# cblock.net
KiCad netlist of a schematic drawn in EAGLE
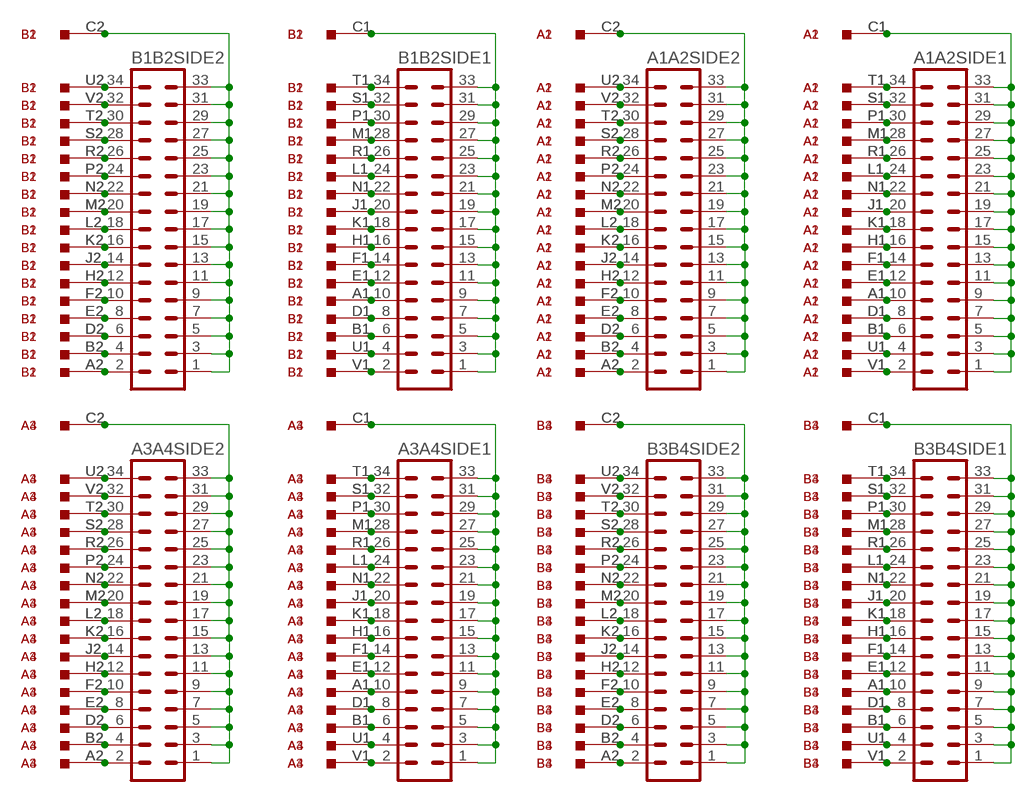
[diagram p0: schematic, sheet 1]

(export (version "E")
  (design (tool "Eeschema 10.0.6"))
  (components
    (comp (ref "A1")
      (value "M916")
      (footprint "eagle-import:H807")
      (libsource (lib "eagle-import") (part "M916"))
    )
    (comp (ref "A1A2SIDE1")
      (value "MA17-2")
      (footprint "eagle-import:MA17-2")
      (libsource (lib "eagle-import") (part "MA17-2"))
    )
    (comp (ref "A1A2SIDE2")
      (value "MA17-2")
      (footprint "eagle-import:MA17-2")
      (libsource (lib "eagle-import") (part "MA17-2"))
    )
    (comp (ref "A2")
      (value "M916")
      (footprint "eagle-import:H807")
      (libsource (lib "eagle-import") (part "M916"))
    )
    (comp (ref "A3")
      (value "M916")
      (footprint "eagle-import:H807")
      (libsource (lib "eagle-import") (part "M916"))
    )
    (comp (ref "A3A4SIDE1")
      (value "MA17-2")
      (footprint "eagle-import:MA17-2")
      (libsource (lib "eagle-import") (part "MA17-2"))
    )
    (comp (ref "A3A4SIDE2")
      (value "MA17-2")
      (footprint "eagle-import:MA17-2")
      (libsource (lib "eagle-import") (part "MA17-2"))
    )
    (comp (ref "A4")
      (value "M916")
      (footprint "eagle-import:H807")
      (libsource (lib "eagle-import") (part "M916"))
    )
    (comp (ref "B1")
      (value "M916")
      (footprint "eagle-import:H807")
      (libsource (lib "eagle-import") (part "M916"))
    )
    (comp (ref "B1B2SIDE1")
      (value "MA17-2")
      (footprint "eagle-import:MA17-2")
      (libsource (lib "eagle-import") (part "MA17-2"))
    )
    (comp (ref "B1B2SIDE2")
      (value "MA17-2")
      (footprint "eagle-import:MA17-2")
      (libsource (lib "eagle-import") (part "MA17-2"))
    )
    (comp (ref "B2")
      (value "M916")
      (footprint "eagle-import:H807")
      (libsource (lib "eagle-import") (part "M916"))
    )
    (comp (ref "B3")
      (value "M916")
      (footprint "eagle-import:H807")
      (libsource (lib "eagle-import") (part "M916"))
    )
    (comp (ref "B3B4SIDE1")
      (value "MA17-2")
      (footprint "eagle-import:MA17-2")
      (libsource (lib "eagle-import") (part "MA17-2"))
    )
    (comp (ref "B3B4SIDE2")
      (value "MA17-2")
      (footprint "eagle-import:MA17-2")
      (libsource (lib "eagle-import") (part "MA17-2"))
    )
    (comp (ref "B4")
      (value "M916")
      (footprint "eagle-import:H807")
      (libsource (lib "eagle-import") (part "M916"))
    )
  )
  (nets
    (net (code "1") (name "Net-(A1A-P$2)") (class "Default")
      (node (ref "A1") (pin "A1") (pinfunction "P$2_A1") (pintype "bidirectional"))
      (node (ref "A1A2SIDE1") (pin "10") (pinfunction "10_10") (pintype "passive"))
      (node (ref "A2") (pin "A1") (pinfunction "P$2_A1") (pintype "bidirectional"))
    )
    (net (code "2") (name "Net-(A1AA-P$2)") (class "Default")
      (node (ref "A1") (pin "R1") (pinfunction "P$2_R1") (pintype "bidirectional"))
      (node (ref "A1A2SIDE1") (pin "26") (pinfunction "26_26") (pintype "passive"))
      (node (ref "A2") (pin "R1") (pinfunction "P$2_R1") (pintype "bidirectional"))
    )
    (net (code "3") (name "Net-(A1AB-P$2)") (class "Default")
      (node (ref "A1") (pin "R2") (pinfunction "P$2_R2") (pintype "bidirectional"))
      (node (ref "A1A2SIDE2") (pin "26") (pinfunction "26_26") (pintype "passive"))
      (node (ref "A2") (pin "R2") (pinfunction "P$2_R2") (pintype "bidirectional"))
    )
    (net (code "4") (name "Net-(A1AC-P$2)") (class "Default")
      (node (ref "A1") (pin "S1") (pinfunction "P$2_S1") (pintype "bidirectional"))
      (node (ref "A1A2SIDE1") (pin "32") (pinfunction "32_32") (pintype "passive"))
      (node (ref "A2") (pin "S1") (pinfunction "P$2_S1") (pintype "bidirectional"))
    )
    (net (code "5") (name "Net-(A1AD-P$2)") (class "Default")
      (node (ref "A1") (pin "S2") (pinfunction "P$2_S2") (pintype "bidirectional"))
      (node (ref "A1A2SIDE2") (pin "28") (pinfunction "28_28") (pintype "passive"))
      (node (ref "A2") (pin "S2") (pinfunction "P$2_S2") (pintype "bidirectional"))
    )
    (net (code "6") (name "Net-(A1AE-P$2)") (class "Default")
      (node (ref "A1") (pin "T1") (pinfunction "P$2_T1") (pintype "bidirectional"))
      (node (ref "A1A2SIDE1") (pin "34") (pinfunction "34_34") (pintype "passive"))
      (node (ref "A2") (pin "T1") (pinfunction "P$2_T1") (pintype "bidirectional"))
    )
    (net (code "7") (name "Net-(A1AF-P$2)") (class "Default")
      (node (ref "A1") (pin "T2") (pinfunction "P$2_T2") (pintype "bidirectional"))
      (node (ref "A1A2SIDE2") (pin "30") (pinfunction "30_30") (pintype "passive"))
      (node (ref "A2") (pin "T2") (pinfunction "P$2_T2") (pintype "bidirectional"))
    )
    (net (code "8") (name "Net-(A1AG-P$2)") (class "Default")
      (node (ref "A1") (pin "U1") (pinfunction "P$2_U1") (pintype "bidirectional"))
      (node (ref "A1A2SIDE1") (pin "4") (pinfunction "4_4") (pintype "passive"))
      (node (ref "A2") (pin "U1") (pinfunction "P$2_U1") (pintype "bidirectional"))
    )
    (net (code "9") (name "Net-(A1AH-P$2)") (class "Default")
      (node (ref "A1") (pin "U2") (pinfunction "P$2_U2") (pintype "bidirectional"))
      (node (ref "A1A2SIDE2") (pin "34") (pinfunction "34_34") (pintype "passive"))
      (node (ref "A2") (pin "U2") (pinfunction "P$2_U2") (pintype "bidirectional"))
    )
    (net (code "10") (name "Net-(A1AI-P$2)") (class "Default")
      (node (ref "A1") (pin "V1") (pinfunction "P$2_V1") (pintype "bidirectional"))
      (node (ref "A1A2SIDE1") (pin "2") (pinfunction "2_2") (pintype "passive"))
      (node (ref "A2") (pin "V1") (pinfunction "P$2_V1") (pintype "bidirectional"))
    )
    (net (code "11") (name "Net-(A1AJ-P$2)") (class "Default")
      (node (ref "A1") (pin "V2") (pinfunction "P$2_V2") (pintype "bidirectional"))
      (node (ref "A1A2SIDE2") (pin "32") (pinfunction "32_32") (pintype "passive"))
      (node (ref "A2") (pin "V2") (pinfunction "P$2_V2") (pintype "bidirectional"))
    )
    (net (code "12") (name "Net-(A1B-P$2)") (class "Default")
      (node (ref "A1") (pin "A2") (pinfunction "P$2_A2") (pintype "bidirectional"))
      (node (ref "A1A2SIDE2") (pin "2") (pinfunction "2_2") (pintype "passive"))
      (node (ref "A2") (pin "A2") (pinfunction "P$2_A2") (pintype "bidirectional"))
    )
    (net (code "13") (name "Net-(A1C-P$2)") (class "Default")
      (node (ref "A1") (pin "B1") (pinfunction "P$2_B1") (pintype "bidirectional"))
      (node (ref "A1A2SIDE1") (pin "6") (pinfunction "6_6") (pintype "passive"))
      (node (ref "A2") (pin "B1") (pinfunction "P$2_B1") (pintype "bidirectional"))
    )
    (net (code "14") (name "Net-(A1D-P$2)") (class "Default")
      (node (ref "A1") (pin "B2") (pinfunction "P$2_B2") (pintype "bidirectional"))
      (node (ref "A1A2SIDE2") (pin "4") (pinfunction "4_4") (pintype "passive"))
      (node (ref "A2") (pin "B2") (pinfunction "P$2_B2") (pintype "bidirectional"))
    )
    (net (code "15") (name "Net-(A1E-P$2)") (class "Default")
      (node (ref "A1") (pin "C1") (pinfunction "P$2_C1") (pintype "bidirectional"))
      (node (ref "A1A2SIDE1") (pin "1") (pinfunction "1_1") (pintype "passive"))
      (node (ref "A1A2SIDE1") (pin "11") (pinfunction "11_11") (pintype "passive"))
      (node (ref "A1A2SIDE1") (pin "13") (pinfunction "13_13") (pintype "passive"))
      (node (ref "A1A2SIDE1") (pin "15") (pinfunction "15_15") (pintype "passive"))
      (node (ref "A1A2SIDE1") (pin "17") (pinfunction "17_17") (pintype "passive"))
      (node (ref "A1A2SIDE1") (pin "19") (pinfunction "19_19") (pintype "passive"))
      (node (ref "A1A2SIDE1") (pin "21") (pinfunction "21_21") (pintype "passive"))
      (node (ref "A1A2SIDE1") (pin "23") (pinfunction "23_23") (pintype "passive"))
      (node (ref "A1A2SIDE1") (pin "25") (pinfunction "25_25") (pintype "passive"))
      (node (ref "A1A2SIDE1") (pin "27") (pinfunction "27_27") (pintype "passive"))
      (node (ref "A1A2SIDE1") (pin "29") (pinfunction "29_29") (pintype "passive"))
      (node (ref "A1A2SIDE1") (pin "3") (pinfunction "3_3") (pintype "passive"))
      (node (ref "A1A2SIDE1") (pin "31") (pinfunction "31_31") (pintype "passive"))
      (node (ref "A1A2SIDE1") (pin "33") (pinfunction "33_33") (pintype "passive"))
      (node (ref "A1A2SIDE1") (pin "5") (pinfunction "5_5") (pintype "passive"))
      (node (ref "A1A2SIDE1") (pin "7") (pinfunction "7_7") (pintype "passive"))
      (node (ref "A1A2SIDE1") (pin "9") (pinfunction "9_9") (pintype "passive"))
      (node (ref "A2") (pin "C1") (pinfunction "P$2_C1") (pintype "bidirectional"))
    )
    (net (code "16") (name "Net-(A1F-P$2)") (class "Default")
      (node (ref "A1") (pin "C2") (pinfunction "P$2_C2") (pintype "bidirectional"))
      (node (ref "A1A2SIDE2") (pin "1") (pinfunction "1_1") (pintype "passive"))
      (node (ref "A1A2SIDE2") (pin "11") (pinfunction "11_11") (pintype "passive"))
      (node (ref "A1A2SIDE2") (pin "13") (pinfunction "13_13") (pintype "passive"))
      (node (ref "A1A2SIDE2") (pin "15") (pinfunction "15_15") (pintype "passive"))
      (node (ref "A1A2SIDE2") (pin "17") (pinfunction "17_17") (pintype "passive"))
      (node (ref "A1A2SIDE2") (pin "19") (pinfunction "19_19") (pintype "passive"))
      (node (ref "A1A2SIDE2") (pin "21") (pinfunction "21_21") (pintype "passive"))
      (node (ref "A1A2SIDE2") (pin "23") (pinfunction "23_23") (pintype "passive"))
      (node (ref "A1A2SIDE2") (pin "25") (pinfunction "25_25") (pintype "passive"))
      (node (ref "A1A2SIDE2") (pin "27") (pinfunction "27_27") (pintype "passive"))
      (node (ref "A1A2SIDE2") (pin "29") (pinfunction "29_29") (pintype "passive"))
      (node (ref "A1A2SIDE2") (pin "3") (pinfunction "3_3") (pintype "passive"))
      (node (ref "A1A2SIDE2") (pin "31") (pinfunction "31_31") (pintype "passive"))
      (node (ref "A1A2SIDE2") (pin "33") (pinfunction "33_33") (pintype "passive"))
      (node (ref "A1A2SIDE2") (pin "5") (pinfunction "5_5") (pintype "passive"))
      (node (ref "A1A2SIDE2") (pin "7") (pinfunction "7_7") (pintype "passive"))
      (node (ref "A1A2SIDE2") (pin "9") (pinfunction "9_9") (pintype "passive"))
      (node (ref "A2") (pin "C2") (pinfunction "P$2_C2") (pintype "bidirectional"))
    )
    (net (code "17") (name "Net-(A1G-P$2)") (class "Default")
      (node (ref "A1") (pin "D1") (pinfunction "P$2_D1") (pintype "bidirectional"))
      (node (ref "A1A2SIDE1") (pin "8") (pinfunction "8_8") (pintype "passive"))
      (node (ref "A2") (pin "D1") (pinfunction "P$2_D1") (pintype "bidirectional"))
    )
    (net (code "18") (name "Net-(A1H-P$2)") (class "Default")
      (node (ref "A1") (pin "D2") (pinfunction "P$2_D2") (pintype "bidirectional"))
      (node (ref "A1A2SIDE2") (pin "6") (pinfunction "6_6") (pintype "passive"))
      (node (ref "A2") (pin "D2") (pinfunction "P$2_D2") (pintype "bidirectional"))
    )
    (net (code "19") (name "Net-(A1I-P$2)") (class "Default")
      (node (ref "A1") (pin "E1") (pinfunction "P$2_E1") (pintype "bidirectional"))
      (node (ref "A1A2SIDE1") (pin "12") (pinfunction "12_12") (pintype "passive"))
      (node (ref "A2") (pin "E1") (pinfunction "P$2_E1") (pintype "bidirectional"))
    )
    (net (code "20") (name "Net-(A1J-P$2)") (class "Default")
      (node (ref "A1") (pin "E2") (pinfunction "P$2_E2") (pintype "bidirectional"))
      (node (ref "A1A2SIDE2") (pin "8") (pinfunction "8_8") (pintype "passive"))
      (node (ref "A2") (pin "E2") (pinfunction "P$2_E2") (pintype "bidirectional"))
    )
    (net (code "21") (name "Net-(A1K-P$2)") (class "Default")
      (node (ref "A1") (pin "F1") (pinfunction "P$2_F1") (pintype "bidirectional"))
      (node (ref "A1A2SIDE1") (pin "14") (pinfunction "14_14") (pintype "passive"))
      (node (ref "A2") (pin "F1") (pinfunction "P$2_F1") (pintype "bidirectional"))
    )
    (net (code "22") (name "Net-(A1L-P$2)") (class "Default")
      (node (ref "A1") (pin "F2") (pinfunction "P$2_F2") (pintype "bidirectional"))
      (node (ref "A1A2SIDE2") (pin "10") (pinfunction "10_10") (pintype "passive"))
      (node (ref "A2") (pin "F2") (pinfunction "P$2_F2") (pintype "bidirectional"))
    )
    (net (code "23") (name "Net-(A1M-P$2)") (class "Default")
      (node (ref "A1") (pin "H1") (pinfunction "P$2_H1") (pintype "bidirectional"))
      (node (ref "A1A2SIDE1") (pin "16") (pinfunction "16_16") (pintype "passive"))
      (node (ref "A2") (pin "H1") (pinfunction "P$2_H1") (pintype "bidirectional"))
    )
    (net (code "24") (name "Net-(A1N-P$2)") (class "Default")
      (node (ref "A1") (pin "H2") (pinfunction "P$2_H2") (pintype "bidirectional"))
      (node (ref "A1A2SIDE2") (pin "12") (pinfunction "12_12") (pintype "passive"))
      (node (ref "A2") (pin "H2") (pinfunction "P$2_H2") (pintype "bidirectional"))
    )
    (net (code "25") (name "Net-(A1O-P$2)") (class "Default")
      (node (ref "A1") (pin "J1") (pinfunction "P$2_J1") (pintype "bidirectional"))
      (node (ref "A1A2SIDE1") (pin "20") (pinfunction "20_20") (pintype "passive"))
      (node (ref "A2") (pin "J1") (pinfunction "P$2_J1") (pintype "bidirectional"))
    )
    (net (code "26") (name "Net-(A1P-P$2)") (class "Default")
      (node (ref "A1") (pin "J2") (pinfunction "P$2_J2") (pintype "bidirectional"))
      (node (ref "A1A2SIDE2") (pin "14") (pinfunction "14_14") (pintype "passive"))
      (node (ref "A2") (pin "J2") (pinfunction "P$2_J2") (pintype "bidirectional"))
    )
    (net (code "27") (name "Net-(A1Q-P$2)") (class "Default")
      (node (ref "A1") (pin "K1") (pinfunction "P$2_K1") (pintype "bidirectional"))
      (node (ref "A1A2SIDE1") (pin "18") (pinfunction "18_18") (pintype "passive"))
      (node (ref "A2") (pin "K1") (pinfunction "P$2_K1") (pintype "bidirectional"))
    )
    (net (code "28") (name "Net-(A1R-P$2)") (class "Default")
      (node (ref "A1") (pin "K2") (pinfunction "P$2_K2") (pintype "bidirectional"))
      (node (ref "A1A2SIDE2") (pin "16") (pinfunction "16_16") (pintype "passive"))
      (node (ref "A2") (pin "K2") (pinfunction "P$2_K2") (pintype "bidirectional"))
    )
    (net (code "29") (name "Net-(A1S-P$2)") (class "Default")
      (node (ref "A1") (pin "L1") (pinfunction "P$2_L1") (pintype "bidirectional"))
      (node (ref "A1A2SIDE1") (pin "24") (pinfunction "24_24") (pintype "passive"))
      (node (ref "A2") (pin "L1") (pinfunction "P$2_L1") (pintype "bidirectional"))
    )
    (net (code "30") (name "Net-(A1T-P$2)") (class "Default")
      (node (ref "A1") (pin "L2") (pinfunction "P$2_L2") (pintype "bidirectional"))
      (node (ref "A1A2SIDE2") (pin "18") (pinfunction "18_18") (pintype "passive"))
      (node (ref "A2") (pin "L2") (pinfunction "P$2_L2") (pintype "bidirectional"))
    )
    (net (code "31") (name "Net-(A1U-P$2)") (class "Default")
      (node (ref "A1") (pin "M1") (pinfunction "P$2_M1") (pintype "bidirectional"))
      (node (ref "A1A2SIDE1") (pin "28") (pinfunction "28_28") (pintype "passive"))
      (node (ref "A2") (pin "M1") (pinfunction "P$2_M1") (pintype "bidirectional"))
    )
    (net (code "32") (name "Net-(A1V-P$2)") (class "Default")
      (node (ref "A1") (pin "M2") (pinfunction "P$2_M2") (pintype "bidirectional"))
      (node (ref "A1A2SIDE2") (pin "20") (pinfunction "20_20") (pintype "passive"))
      (node (ref "A2") (pin "M2") (pinfunction "P$2_M2") (pintype "bidirectional"))
    )
    (net (code "33") (name "Net-(A1W-P$2)") (class "Default")
      (node (ref "A1") (pin "N1") (pinfunction "P$2_N1") (pintype "bidirectional"))
      (node (ref "A1A2SIDE1") (pin "22") (pinfunction "22_22") (pintype "passive"))
      (node (ref "A2") (pin "N1") (pinfunction "P$2_N1") (pintype "bidirectional"))
    )
    (net (code "34") (name "Net-(A1X-P$2)") (class "Default")
      (node (ref "A1") (pin "N2") (pinfunction "P$2_N2") (pintype "bidirectional"))
      (node (ref "A1A2SIDE2") (pin "22") (pinfunction "22_22") (pintype "passive"))
      (node (ref "A2") (pin "N2") (pinfunction "P$2_N2") (pintype "bidirectional"))
    )
    (net (code "35") (name "Net-(A1Y-P$2)") (class "Default")
      (node (ref "A1") (pin "P1") (pinfunction "P$2_P1") (pintype "bidirectional"))
      (node (ref "A1A2SIDE1") (pin "30") (pinfunction "30_30") (pintype "passive"))
      (node (ref "A2") (pin "P1") (pinfunction "P$2_P1") (pintype "bidirectional"))
    )
    (net (code "36") (name "Net-(A1Z-P$2)") (class "Default")
      (node (ref "A1") (pin "P2") (pinfunction "P$2_P2") (pintype "bidirectional"))
      (node (ref "A1A2SIDE2") (pin "24") (pinfunction "24_24") (pintype "passive"))
      (node (ref "A2") (pin "P2") (pinfunction "P$2_P2") (pintype "bidirectional"))
    )
    (net (code "37") (name "Net-(A3A-P$2)") (class "Default")
      (node (ref "A3") (pin "A1") (pinfunction "P$2_A1") (pintype "bidirectional"))
      (node (ref "A3A4SIDE1") (pin "10") (pinfunction "10_10") (pintype "passive"))
      (node (ref "A4") (pin "A1") (pinfunction "P$2_A1") (pintype "bidirectional"))
    )
    (net (code "38") (name "Net-(A3AA-P$2)") (class "Default")
      (node (ref "A3") (pin "R1") (pinfunction "P$2_R1") (pintype "bidirectional"))
      (node (ref "A3A4SIDE1") (pin "26") (pinfunction "26_26") (pintype "passive"))
      (node (ref "A4") (pin "R1") (pinfunction "P$2_R1") (pintype "bidirectional"))
    )
    (net (code "39") (name "Net-(A3AB-P$2)") (class "Default")
      (node (ref "A3") (pin "R2") (pinfunction "P$2_R2") (pintype "bidirectional"))
      (node (ref "A3A4SIDE2") (pin "26") (pinfunction "26_26") (pintype "passive"))
      (node (ref "A4") (pin "R2") (pinfunction "P$2_R2") (pintype "bidirectional"))
    )
    (net (code "40") (name "Net-(A3AC-P$2)") (class "Default")
      (node (ref "A3") (pin "S1") (pinfunction "P$2_S1") (pintype "bidirectional"))
      (node (ref "A3A4SIDE1") (pin "32") (pinfunction "32_32") (pintype "passive"))
      (node (ref "A4") (pin "S1") (pinfunction "P$2_S1") (pintype "bidirectional"))
    )
    (net (code "41") (name "Net-(A3AD-P$2)") (class "Default")
      (node (ref "A3") (pin "S2") (pinfunction "P$2_S2") (pintype "bidirectional"))
      (node (ref "A3A4SIDE2") (pin "28") (pinfunction "28_28") (pintype "passive"))
      (node (ref "A4") (pin "S2") (pinfunction "P$2_S2") (pintype "bidirectional"))
    )
    (net (code "42") (name "Net-(A3AE-P$2)") (class "Default")
      (node (ref "A3") (pin "T1") (pinfunction "P$2_T1") (pintype "bidirectional"))
      (node (ref "A3A4SIDE1") (pin "34") (pinfunction "34_34") (pintype "passive"))
      (node (ref "A4") (pin "T1") (pinfunction "P$2_T1") (pintype "bidirectional"))
    )
    (net (code "43") (name "Net-(A3AF-P$2)") (class "Default")
      (node (ref "A3") (pin "T2") (pinfunction "P$2_T2") (pintype "bidirectional"))
      (node (ref "A3A4SIDE2") (pin "30") (pinfunction "30_30") (pintype "passive"))
      (node (ref "A4") (pin "T2") (pinfunction "P$2_T2") (pintype "bidirectional"))
    )
    (net (code "44") (name "Net-(A3AG-P$2)") (class "Default")
      (node (ref "A3") (pin "U1") (pinfunction "P$2_U1") (pintype "bidirectional"))
      (node (ref "A3A4SIDE1") (pin "4") (pinfunction "4_4") (pintype "passive"))
      (node (ref "A4") (pin "U1") (pinfunction "P$2_U1") (pintype "bidirectional"))
    )
    (net (code "45") (name "Net-(A3AH-P$2)") (class "Default")
      (node (ref "A3") (pin "U2") (pinfunction "P$2_U2") (pintype "bidirectional"))
      (node (ref "A3A4SIDE2") (pin "34") (pinfunction "34_34") (pintype "passive"))
      (node (ref "A4") (pin "U2") (pinfunction "P$2_U2") (pintype "bidirectional"))
    )
    (net (code "46") (name "Net-(A3AI-P$2)") (class "Default")
      (node (ref "A3") (pin "V1") (pinfunction "P$2_V1") (pintype "bidirectional"))
      (node (ref "A3A4SIDE1") (pin "2") (pinfunction "2_2") (pintype "passive"))
      (node (ref "A4") (pin "V1") (pinfunction "P$2_V1") (pintype "bidirectional"))
    )
    (net (code "47") (name "Net-(A3AJ-P$2)") (class "Default")
      (node (ref "A3") (pin "V2") (pinfunction "P$2_V2") (pintype "bidirectional"))
      (node (ref "A3A4SIDE2") (pin "32") (pinfunction "32_32") (pintype "passive"))
      (node (ref "A4") (pin "V2") (pinfunction "P$2_V2") (pintype "bidirectional"))
    )
    (net (code "48") (name "Net-(A3B-P$2)") (class "Default")
      (node (ref "A3") (pin "A2") (pinfunction "P$2_A2") (pintype "bidirectional"))
      (node (ref "A3A4SIDE2") (pin "2") (pinfunction "2_2") (pintype "passive"))
      (node (ref "A4") (pin "A2") (pinfunction "P$2_A2") (pintype "bidirectional"))
    )
    (net (code "49") (name "Net-(A3C-P$2)") (class "Default")
      (node (ref "A3") (pin "B1") (pinfunction "P$2_B1") (pintype "bidirectional"))
      (node (ref "A3A4SIDE1") (pin "6") (pinfunction "6_6") (pintype "passive"))
      (node (ref "A4") (pin "B1") (pinfunction "P$2_B1") (pintype "bidirectional"))
    )
    (net (code "50") (name "Net-(A3D-P$2)") (class "Default")
      (node (ref "A3") (pin "B2") (pinfunction "P$2_B2") (pintype "bidirectional"))
      (node (ref "A3A4SIDE2") (pin "4") (pinfunction "4_4") (pintype "passive"))
      (node (ref "A4") (pin "B2") (pinfunction "P$2_B2") (pintype "bidirectional"))
    )
    (net (code "51") (name "Net-(A3E-P$2)") (class "Default")
      (node (ref "A3") (pin "C1") (pinfunction "P$2_C1") (pintype "bidirectional"))
      (node (ref "A3A4SIDE1") (pin "1") (pinfunction "1_1") (pintype "passive"))
      (node (ref "A3A4SIDE1") (pin "11") (pinfunction "11_11") (pintype "passive"))
      (node (ref "A3A4SIDE1") (pin "13") (pinfunction "13_13") (pintype "passive"))
      (node (ref "A3A4SIDE1") (pin "15") (pinfunction "15_15") (pintype "passive"))
      (node (ref "A3A4SIDE1") (pin "17") (pinfunction "17_17") (pintype "passive"))
      (node (ref "A3A4SIDE1") (pin "19") (pinfunction "19_19") (pintype "passive"))
      (node (ref "A3A4SIDE1") (pin "21") (pinfunction "21_21") (pintype "passive"))
      (node (ref "A3A4SIDE1") (pin "23") (pinfunction "23_23") (pintype "passive"))
      (node (ref "A3A4SIDE1") (pin "25") (pinfunction "25_25") (pintype "passive"))
      (node (ref "A3A4SIDE1") (pin "27") (pinfunction "27_27") (pintype "passive"))
      (node (ref "A3A4SIDE1") (pin "29") (pinfunction "29_29") (pintype "passive"))
      (node (ref "A3A4SIDE1") (pin "3") (pinfunction "3_3") (pintype "passive"))
      (node (ref "A3A4SIDE1") (pin "31") (pinfunction "31_31") (pintype "passive"))
      (node (ref "A3A4SIDE1") (pin "33") (pinfunction "33_33") (pintype "passive"))
      (node (ref "A3A4SIDE1") (pin "5") (pinfunction "5_5") (pintype "passive"))
      (node (ref "A3A4SIDE1") (pin "7") (pinfunction "7_7") (pintype "passive"))
      (node (ref "A3A4SIDE1") (pin "9") (pinfunction "9_9") (pintype "passive"))
      (node (ref "A4") (pin "C1") (pinfunction "P$2_C1") (pintype "bidirectional"))
    )
    (net (code "52") (name "Net-(A3F-P$2)") (class "Default")
      (node (ref "A3") (pin "C2") (pinfunction "P$2_C2") (pintype "bidirectional"))
      (node (ref "A3A4SIDE2") (pin "1") (pinfunction "1_1") (pintype "passive"))
      (node (ref "A3A4SIDE2") (pin "11") (pinfunction "11_11") (pintype "passive"))
      (node (ref "A3A4SIDE2") (pin "13") (pinfunction "13_13") (pintype "passive"))
      (node (ref "A3A4SIDE2") (pin "15") (pinfunction "15_15") (pintype "passive"))
      (node (ref "A3A4SIDE2") (pin "17") (pinfunction "17_17") (pintype "passive"))
      (node (ref "A3A4SIDE2") (pin "19") (pinfunction "19_19") (pintype "passive"))
      (node (ref "A3A4SIDE2") (pin "21") (pinfunction "21_21") (pintype "passive"))
      (node (ref "A3A4SIDE2") (pin "23") (pinfunction "23_23") (pintype "passive"))
      (node (ref "A3A4SIDE2") (pin "25") (pinfunction "25_25") (pintype "passive"))
      (node (ref "A3A4SIDE2") (pin "27") (pinfunction "27_27") (pintype "passive"))
      (node (ref "A3A4SIDE2") (pin "29") (pinfunction "29_29") (pintype "passive"))
      (node (ref "A3A4SIDE2") (pin "3") (pinfunction "3_3") (pintype "passive"))
      (node (ref "A3A4SIDE2") (pin "31") (pinfunction "31_31") (pintype "passive"))
      (node (ref "A3A4SIDE2") (pin "33") (pinfunction "33_33") (pintype "passive"))
      (node (ref "A3A4SIDE2") (pin "5") (pinfunction "5_5") (pintype "passive"))
      (node (ref "A3A4SIDE2") (pin "7") (pinfunction "7_7") (pintype "passive"))
      (node (ref "A3A4SIDE2") (pin "9") (pinfunction "9_9") (pintype "passive"))
      (node (ref "A4") (pin "C2") (pinfunction "P$2_C2") (pintype "bidirectional"))
    )
    (net (code "53") (name "Net-(A3G-P$2)") (class "Default")
      (node (ref "A3") (pin "D1") (pinfunction "P$2_D1") (pintype "bidirectional"))
      (node (ref "A3A4SIDE1") (pin "8") (pinfunction "8_8") (pintype "passive"))
      (node (ref "A4") (pin "D1") (pinfunction "P$2_D1") (pintype "bidirectional"))
    )
    (net (code "54") (name "Net-(A3H-P$2)") (class "Default")
      (node (ref "A3") (pin "D2") (pinfunction "P$2_D2") (pintype "bidirectional"))
      (node (ref "A3A4SIDE2") (pin "6") (pinfunction "6_6") (pintype "passive"))
      (node (ref "A4") (pin "D2") (pinfunction "P$2_D2") (pintype "bidirectional"))
    )
    (net (code "55") (name "Net-(A3I-P$2)") (class "Default")
      (node (ref "A3") (pin "E1") (pinfunction "P$2_E1") (pintype "bidirectional"))
      (node (ref "A3A4SIDE1") (pin "12") (pinfunction "12_12") (pintype "passive"))
      (node (ref "A4") (pin "E1") (pinfunction "P$2_E1") (pintype "bidirectional"))
    )
    (net (code "56") (name "Net-(A3J-P$2)") (class "Default")
      (node (ref "A3") (pin "E2") (pinfunction "P$2_E2") (pintype "bidirectional"))
      (node (ref "A3A4SIDE2") (pin "8") (pinfunction "8_8") (pintype "passive"))
      (node (ref "A4") (pin "E2") (pinfunction "P$2_E2") (pintype "bidirectional"))
    )
    (net (code "57") (name "Net-(A3K-P$2)") (class "Default")
      (node (ref "A3") (pin "F1") (pinfunction "P$2_F1") (pintype "bidirectional"))
      (node (ref "A3A4SIDE1") (pin "14") (pinfunction "14_14") (pintype "passive"))
      (node (ref "A4") (pin "F1") (pinfunction "P$2_F1") (pintype "bidirectional"))
    )
    (net (code "58") (name "Net-(A3L-P$2)") (class "Default")
      (node (ref "A3") (pin "F2") (pinfunction "P$2_F2") (pintype "bidirectional"))
      (node (ref "A3A4SIDE2") (pin "10") (pinfunction "10_10") (pintype "passive"))
      (node (ref "A4") (pin "F2") (pinfunction "P$2_F2") (pintype "bidirectional"))
    )
    (net (code "59") (name "Net-(A3M-P$2)") (class "Default")
      (node (ref "A3") (pin "H1") (pinfunction "P$2_H1") (pintype "bidirectional"))
      (node (ref "A3A4SIDE1") (pin "16") (pinfunction "16_16") (pintype "passive"))
      (node (ref "A4") (pin "H1") (pinfunction "P$2_H1") (pintype "bidirectional"))
    )
    (net (code "60") (name "Net-(A3N-P$2)") (class "Default")
      (node (ref "A3") (pin "H2") (pinfunction "P$2_H2") (pintype "bidirectional"))
      (node (ref "A3A4SIDE2") (pin "12") (pinfunction "12_12") (pintype "passive"))
      (node (ref "A4") (pin "H2") (pinfunction "P$2_H2") (pintype "bidirectional"))
    )
    (net (code "61") (name "Net-(A3O-P$2)") (class "Default")
      (node (ref "A3") (pin "J1") (pinfunction "P$2_J1") (pintype "bidirectional"))
      (node (ref "A3A4SIDE1") (pin "20") (pinfunction "20_20") (pintype "passive"))
      (node (ref "A4") (pin "J1") (pinfunction "P$2_J1") (pintype "bidirectional"))
    )
    (net (code "62") (name "Net-(A3P-P$2)") (class "Default")
      (node (ref "A3") (pin "J2") (pinfunction "P$2_J2") (pintype "bidirectional"))
      (node (ref "A3A4SIDE2") (pin "14") (pinfunction "14_14") (pintype "passive"))
      (node (ref "A4") (pin "J2") (pinfunction "P$2_J2") (pintype "bidirectional"))
    )
    (net (code "63") (name "Net-(A3Q-P$2)") (class "Default")
      (node (ref "A3") (pin "K1") (pinfunction "P$2_K1") (pintype "bidirectional"))
      (node (ref "A3A4SIDE1") (pin "18") (pinfunction "18_18") (pintype "passive"))
      (node (ref "A4") (pin "K1") (pinfunction "P$2_K1") (pintype "bidirectional"))
    )
    (net (code "64") (name "Net-(A3R-P$2)") (class "Default")
      (node (ref "A3") (pin "K2") (pinfunction "P$2_K2") (pintype "bidirectional"))
      (node (ref "A3A4SIDE2") (pin "16") (pinfunction "16_16") (pintype "passive"))
      (node (ref "A4") (pin "K2") (pinfunction "P$2_K2") (pintype "bidirectional"))
    )
    (net (code "65") (name "Net-(A3S-P$2)") (class "Default")
      (node (ref "A3") (pin "L1") (pinfunction "P$2_L1") (pintype "bidirectional"))
      (node (ref "A3A4SIDE1") (pin "24") (pinfunction "24_24") (pintype "passive"))
      (node (ref "A4") (pin "L1") (pinfunction "P$2_L1") (pintype "bidirectional"))
    )
    (net (code "66") (name "Net-(A3T-P$2)") (class "Default")
      (node (ref "A3") (pin "L2") (pinfunction "P$2_L2") (pintype "bidirectional"))
      (node (ref "A3A4SIDE2") (pin "18") (pinfunction "18_18") (pintype "passive"))
      (node (ref "A4") (pin "L2") (pinfunction "P$2_L2") (pintype "bidirectional"))
    )
    (net (code "67") (name "Net-(A3U-P$2)") (class "Default")
      (node (ref "A3") (pin "M1") (pinfunction "P$2_M1") (pintype "bidirectional"))
      (node (ref "A3A4SIDE1") (pin "28") (pinfunction "28_28") (pintype "passive"))
      (node (ref "A4") (pin "M1") (pinfunction "P$2_M1") (pintype "bidirectional"))
    )
    (net (code "68") (name "Net-(A3V-P$2)") (class "Default")
      (node (ref "A3") (pin "M2") (pinfunction "P$2_M2") (pintype "bidirectional"))
      (node (ref "A3A4SIDE2") (pin "20") (pinfunction "20_20") (pintype "passive"))
      (node (ref "A4") (pin "M2") (pinfunction "P$2_M2") (pintype "bidirectional"))
    )
    (net (code "69") (name "Net-(A3W-P$2)") (class "Default")
      (node (ref "A3") (pin "N1") (pinfunction "P$2_N1") (pintype "bidirectional"))
      (node (ref "A3A4SIDE1") (pin "22") (pinfunction "22_22") (pintype "passive"))
      (node (ref "A4") (pin "N1") (pinfunction "P$2_N1") (pintype "bidirectional"))
    )
    (net (code "70") (name "Net-(A3X-P$2)") (class "Default")
      (node (ref "A3") (pin "N2") (pinfunction "P$2_N2") (pintype "bidirectional"))
      (node (ref "A3A4SIDE2") (pin "22") (pinfunction "22_22") (pintype "passive"))
      (node (ref "A4") (pin "N2") (pinfunction "P$2_N2") (pintype "bidirectional"))
    )
    (net (code "71") (name "Net-(A3Y-P$2)") (class "Default")
      (node (ref "A3") (pin "P1") (pinfunction "P$2_P1") (pintype "bidirectional"))
      (node (ref "A3A4SIDE1") (pin "30") (pinfunction "30_30") (pintype "passive"))
      (node (ref "A4") (pin "P1") (pinfunction "P$2_P1") (pintype "bidirectional"))
    )
    (net (code "72") (name "Net-(A3Z-P$2)") (class "Default")
      (node (ref "A3") (pin "P2") (pinfunction "P$2_P2") (pintype "bidirectional"))
      (node (ref "A3A4SIDE2") (pin "24") (pinfunction "24_24") (pintype "passive"))
      (node (ref "A4") (pin "P2") (pinfunction "P$2_P2") (pintype "bidirectional"))
    )
    (net (code "73") (name "Net-(B1A-P$2)") (class "Default")
      (node (ref "B1") (pin "A1") (pinfunction "P$2_A1") (pintype "bidirectional"))
      (node (ref "B1B2SIDE1") (pin "10") (pinfunction "10_10") (pintype "passive"))
      (node (ref "B2") (pin "A1") (pinfunction "P$2_A1") (pintype "bidirectional"))
    )
    (net (code "74") (name "Net-(B1AA-P$2)") (class "Default")
      (node (ref "B1") (pin "R1") (pinfunction "P$2_R1") (pintype "bidirectional"))
      (node (ref "B1B2SIDE1") (pin "26") (pinfunction "26_26") (pintype "passive"))
      (node (ref "B2") (pin "R1") (pinfunction "P$2_R1") (pintype "bidirectional"))
    )
    (net (code "75") (name "Net-(B1AB-P$2)") (class "Default")
      (node (ref "B1") (pin "R2") (pinfunction "P$2_R2") (pintype "bidirectional"))
      (node (ref "B1B2SIDE2") (pin "26") (pinfunction "26_26") (pintype "passive"))
      (node (ref "B2") (pin "R2") (pinfunction "P$2_R2") (pintype "bidirectional"))
    )
    (net (code "76") (name "Net-(B1AC-P$2)") (class "Default")
      (node (ref "B1") (pin "S1") (pinfunction "P$2_S1") (pintype "bidirectional"))
      (node (ref "B1B2SIDE1") (pin "32") (pinfunction "32_32") (pintype "passive"))
      (node (ref "B2") (pin "S1") (pinfunction "P$2_S1") (pintype "bidirectional"))
    )
    (net (code "77") (name "Net-(B1AD-P$2)") (class "Default")
      (node (ref "B1") (pin "S2") (pinfunction "P$2_S2") (pintype "bidirectional"))
      (node (ref "B1B2SIDE2") (pin "28") (pinfunction "28_28") (pintype "passive"))
      (node (ref "B2") (pin "S2") (pinfunction "P$2_S2") (pintype "bidirectional"))
    )
    (net (code "78") (name "Net-(B1AE-P$2)") (class "Default")
      (node (ref "B1") (pin "T1") (pinfunction "P$2_T1") (pintype "bidirectional"))
      (node (ref "B1B2SIDE1") (pin "34") (pinfunction "34_34") (pintype "passive"))
      (node (ref "B2") (pin "T1") (pinfunction "P$2_T1") (pintype "bidirectional"))
    )
    (net (code "79") (name "Net-(B1AF-P$2)") (class "Default")
      (node (ref "B1") (pin "T2") (pinfunction "P$2_T2") (pintype "bidirectional"))
      (node (ref "B1B2SIDE2") (pin "30") (pinfunction "30_30") (pintype "passive"))
      (node (ref "B2") (pin "T2") (pinfunction "P$2_T2") (pintype "bidirectional"))
    )
    (net (code "80") (name "Net-(B1AG-P$2)") (class "Default")
      (node (ref "B1") (pin "U1") (pinfunction "P$2_U1") (pintype "bidirectional"))
      (node (ref "B1B2SIDE1") (pin "4") (pinfunction "4_4") (pintype "passive"))
      (node (ref "B2") (pin "U1") (pinfunction "P$2_U1") (pintype "bidirectional"))
    )
    (net (code "81") (name "Net-(B1AH-P$2)") (class "Default")
      (node (ref "B1") (pin "U2") (pinfunction "P$2_U2") (pintype "bidirectional"))
      (node (ref "B1B2SIDE2") (pin "34") (pinfunction "34_34") (pintype "passive"))
      (node (ref "B2") (pin "U2") (pinfunction "P$2_U2") (pintype "bidirectional"))
    )
    (net (code "82") (name "Net-(B1AI-P$2)") (class "Default")
      (node (ref "B1") (pin "V1") (pinfunction "P$2_V1") (pintype "bidirectional"))
      (node (ref "B1B2SIDE1") (pin "2") (pinfunction "2_2") (pintype "passive"))
      (node (ref "B2") (pin "V1") (pinfunction "P$2_V1") (pintype "bidirectional"))
    )
    (net (code "83") (name "Net-(B1AJ-P$2)") (class "Default")
      (node (ref "B1") (pin "V2") (pinfunction "P$2_V2") (pintype "bidirectional"))
      (node (ref "B1B2SIDE2") (pin "32") (pinfunction "32_32") (pintype "passive"))
      (node (ref "B2") (pin "V2") (pinfunction "P$2_V2") (pintype "bidirectional"))
    )
    (net (code "84") (name "Net-(B1B-P$2)") (class "Default")
      (node (ref "B1") (pin "A2") (pinfunction "P$2_A2") (pintype "bidirectional"))
      (node (ref "B1B2SIDE2") (pin "2") (pinfunction "2_2") (pintype "passive"))
      (node (ref "B2") (pin "A2") (pinfunction "P$2_A2") (pintype "bidirectional"))
    )
    (net (code "85") (name "Net-(B1C-P$2)") (class "Default")
      (node (ref "B1") (pin "B1") (pinfunction "P$2_B1") (pintype "bidirectional"))
      (node (ref "B1B2SIDE1") (pin "6") (pinfunction "6_6") (pintype "passive"))
      (node (ref "B2") (pin "B1") (pinfunction "P$2_B1") (pintype "bidirectional"))
    )
    (net (code "86") (name "Net-(B1D-P$2)") (class "Default")
      (node (ref "B1") (pin "B2") (pinfunction "P$2_B2") (pintype "bidirectional"))
      (node (ref "B1B2SIDE2") (pin "4") (pinfunction "4_4") (pintype "passive"))
      (node (ref "B2") (pin "B2") (pinfunction "P$2_B2") (pintype "bidirectional"))
    )
    (net (code "87") (name "Net-(B1E-P$2)") (class "Default")
      (node (ref "B1") (pin "C1") (pinfunction "P$2_C1") (pintype "bidirectional"))
      (node (ref "B1B2SIDE1") (pin "1") (pinfunction "1_1") (pintype "passive"))
      (node (ref "B1B2SIDE1") (pin "11") (pinfunction "11_11") (pintype "passive"))
      (node (ref "B1B2SIDE1") (pin "13") (pinfunction "13_13") (pintype "passive"))
      (node (ref "B1B2SIDE1") (pin "15") (pinfunction "15_15") (pintype "passive"))
      (node (ref "B1B2SIDE1") (pin "17") (pinfunction "17_17") (pintype "passive"))
      (node (ref "B1B2SIDE1") (pin "19") (pinfunction "19_19") (pintype "passive"))
      (node (ref "B1B2SIDE1") (pin "21") (pinfunction "21_21") (pintype "passive"))
      (node (ref "B1B2SIDE1") (pin "23") (pinfunction "23_23") (pintype "passive"))
      (node (ref "B1B2SIDE1") (pin "25") (pinfunction "25_25") (pintype "passive"))
      (node (ref "B1B2SIDE1") (pin "27") (pinfunction "27_27") (pintype "passive"))
      (node (ref "B1B2SIDE1") (pin "29") (pinfunction "29_29") (pintype "passive"))
      (node (ref "B1B2SIDE1") (pin "3") (pinfunction "3_3") (pintype "passive"))
      (node (ref "B1B2SIDE1") (pin "31") (pinfunction "31_31") (pintype "passive"))
      (node (ref "B1B2SIDE1") (pin "33") (pinfunction "33_33") (pintype "passive"))
      (node (ref "B1B2SIDE1") (pin "5") (pinfunction "5_5") (pintype "passive"))
      (node (ref "B1B2SIDE1") (pin "7") (pinfunction "7_7") (pintype "passive"))
      (node (ref "B1B2SIDE1") (pin "9") (pinfunction "9_9") (pintype "passive"))
      (node (ref "B2") (pin "C1") (pinfunction "P$2_C1") (pintype "bidirectional"))
    )
    (net (code "88") (name "Net-(B1F-P$2)") (class "Default")
      (node (ref "B1") (pin "C2") (pinfunction "P$2_C2") (pintype "bidirectional"))
      (node (ref "B1B2SIDE2") (pin "1") (pinfunction "1_1") (pintype "passive"))
      (node (ref "B1B2SIDE2") (pin "11") (pinfunction "11_11") (pintype "passive"))
      (node (ref "B1B2SIDE2") (pin "13") (pinfunction "13_13") (pintype "passive"))
      (node (ref "B1B2SIDE2") (pin "15") (pinfunction "15_15") (pintype "passive"))
      (node (ref "B1B2SIDE2") (pin "17") (pinfunction "17_17") (pintype "passive"))
      (node (ref "B1B2SIDE2") (pin "19") (pinfunction "19_19") (pintype "passive"))
      (node (ref "B1B2SIDE2") (pin "21") (pinfunction "21_21") (pintype "passive"))
      (node (ref "B1B2SIDE2") (pin "23") (pinfunction "23_23") (pintype "passive"))
      (node (ref "B1B2SIDE2") (pin "25") (pinfunction "25_25") (pintype "passive"))
      (node (ref "B1B2SIDE2") (pin "27") (pinfunction "27_27") (pintype "passive"))
      (node (ref "B1B2SIDE2") (pin "29") (pinfunction "29_29") (pintype "passive"))
      (node (ref "B1B2SIDE2") (pin "3") (pinfunction "3_3") (pintype "passive"))
      (node (ref "B1B2SIDE2") (pin "31") (pinfunction "31_31") (pintype "passive"))
      (node (ref "B1B2SIDE2") (pin "33") (pinfunction "33_33") (pintype "passive"))
      (node (ref "B1B2SIDE2") (pin "5") (pinfunction "5_5") (pintype "passive"))
      (node (ref "B1B2SIDE2") (pin "7") (pinfunction "7_7") (pintype "passive"))
      (node (ref "B1B2SIDE2") (pin "9") (pinfunction "9_9") (pintype "passive"))
      (node (ref "B2") (pin "C2") (pinfunction "P$2_C2") (pintype "bidirectional"))
    )
    (net (code "89") (name "Net-(B1G-P$2)") (class "Default")
      (node (ref "B1") (pin "D1") (pinfunction "P$2_D1") (pintype "bidirectional"))
      (node (ref "B1B2SIDE1") (pin "8") (pinfunction "8_8") (pintype "passive"))
      (node (ref "B2") (pin "D1") (pinfunction "P$2_D1") (pintype "bidirectional"))
    )
    (net (code "90") (name "Net-(B1H-P$2)") (class "Default")
      (node (ref "B1") (pin "D2") (pinfunction "P$2_D2") (pintype "bidirectional"))
      (node (ref "B1B2SIDE2") (pin "6") (pinfunction "6_6") (pintype "passive"))
      (node (ref "B2") (pin "D2") (pinfunction "P$2_D2") (pintype "bidirectional"))
    )
    (net (code "91") (name "Net-(B1I-P$2)") (class "Default")
      (node (ref "B1") (pin "E1") (pinfunction "P$2_E1") (pintype "bidirectional"))
      (node (ref "B1B2SIDE1") (pin "12") (pinfunction "12_12") (pintype "passive"))
      (node (ref "B2") (pin "E1") (pinfunction "P$2_E1") (pintype "bidirectional"))
    )
    (net (code "92") (name "Net-(B1J-P$2)") (class "Default")
      (node (ref "B1") (pin "E2") (pinfunction "P$2_E2") (pintype "bidirectional"))
      (node (ref "B1B2SIDE2") (pin "8") (pinfunction "8_8") (pintype "passive"))
      (node (ref "B2") (pin "E2") (pinfunction "P$2_E2") (pintype "bidirectional"))
    )
    (net (code "93") (name "Net-(B1K-P$2)") (class "Default")
      (node (ref "B1") (pin "F1") (pinfunction "P$2_F1") (pintype "bidirectional"))
      (node (ref "B1B2SIDE1") (pin "14") (pinfunction "14_14") (pintype "passive"))
      (node (ref "B2") (pin "F1") (pinfunction "P$2_F1") (pintype "bidirectional"))
    )
    (net (code "94") (name "Net-(B1L-P$2)") (class "Default")
      (node (ref "B1") (pin "F2") (pinfunction "P$2_F2") (pintype "bidirectional"))
      (node (ref "B1B2SIDE2") (pin "10") (pinfunction "10_10") (pintype "passive"))
      (node (ref "B2") (pin "F2") (pinfunction "P$2_F2") (pintype "bidirectional"))
    )
    (net (code "95") (name "Net-(B1M-P$2)") (class "Default")
      (node (ref "B1") (pin "H1") (pinfunction "P$2_H1") (pintype "bidirectional"))
      (node (ref "B1B2SIDE1") (pin "16") (pinfunction "16_16") (pintype "passive"))
      (node (ref "B2") (pin "H1") (pinfunction "P$2_H1") (pintype "bidirectional"))
    )
    (net (code "96") (name "Net-(B1N-P$2)") (class "Default")
      (node (ref "B1") (pin "H2") (pinfunction "P$2_H2") (pintype "bidirectional"))
      (node (ref "B1B2SIDE2") (pin "12") (pinfunction "12_12") (pintype "passive"))
      (node (ref "B2") (pin "H2") (pinfunction "P$2_H2") (pintype "bidirectional"))
    )
    (net (code "97") (name "Net-(B1O-P$2)") (class "Default")
      (node (ref "B1") (pin "J1") (pinfunction "P$2_J1") (pintype "bidirectional"))
      (node (ref "B1B2SIDE1") (pin "20") (pinfunction "20_20") (pintype "passive"))
      (node (ref "B2") (pin "J1") (pinfunction "P$2_J1") (pintype "bidirectional"))
    )
    (net (code "98") (name "Net-(B1P-P$2)") (class "Default")
      (node (ref "B1") (pin "J2") (pinfunction "P$2_J2") (pintype "bidirectional"))
      (node (ref "B1B2SIDE2") (pin "14") (pinfunction "14_14") (pintype "passive"))
      (node (ref "B2") (pin "J2") (pinfunction "P$2_J2") (pintype "bidirectional"))
    )
    (net (code "99") (name "Net-(B1Q-P$2)") (class "Default")
      (node (ref "B1") (pin "K1") (pinfunction "P$2_K1") (pintype "bidirectional"))
      (node (ref "B1B2SIDE1") (pin "18") (pinfunction "18_18") (pintype "passive"))
      (node (ref "B2") (pin "K1") (pinfunction "P$2_K1") (pintype "bidirectional"))
    )
    (net (code "100") (name "Net-(B1R-P$2)") (class "Default")
      (node (ref "B1") (pin "K2") (pinfunction "P$2_K2") (pintype "bidirectional"))
      (node (ref "B1B2SIDE2") (pin "16") (pinfunction "16_16") (pintype "passive"))
      (node (ref "B2") (pin "K2") (pinfunction "P$2_K2") (pintype "bidirectional"))
    )
    (net (code "101") (name "Net-(B1S-P$2)") (class "Default")
      (node (ref "B1") (pin "L1") (pinfunction "P$2_L1") (pintype "bidirectional"))
      (node (ref "B1B2SIDE1") (pin "24") (pinfunction "24_24") (pintype "passive"))
      (node (ref "B2") (pin "L1") (pinfunction "P$2_L1") (pintype "bidirectional"))
    )
    (net (code "102") (name "Net-(B1T-P$2)") (class "Default")
      (node (ref "B1") (pin "L2") (pinfunction "P$2_L2") (pintype "bidirectional"))
      (node (ref "B1B2SIDE2") (pin "18") (pinfunction "18_18") (pintype "passive"))
      (node (ref "B2") (pin "L2") (pinfunction "P$2_L2") (pintype "bidirectional"))
    )
    (net (code "103") (name "Net-(B1U-P$2)") (class "Default")
      (node (ref "B1") (pin "M1") (pinfunction "P$2_M1") (pintype "bidirectional"))
      (node (ref "B1B2SIDE1") (pin "28") (pinfunction "28_28") (pintype "passive"))
      (node (ref "B2") (pin "M1") (pinfunction "P$2_M1") (pintype "bidirectional"))
    )
    (net (code "104") (name "Net-(B1V-P$2)") (class "Default")
      (node (ref "B1") (pin "M2") (pinfunction "P$2_M2") (pintype "bidirectional"))
      (node (ref "B1B2SIDE2") (pin "20") (pinfunction "20_20") (pintype "passive"))
      (node (ref "B2") (pin "M2") (pinfunction "P$2_M2") (pintype "bidirectional"))
    )
    (net (code "105") (name "Net-(B1W-P$2)") (class "Default")
      (node (ref "B1") (pin "N1") (pinfunction "P$2_N1") (pintype "bidirectional"))
      (node (ref "B1B2SIDE1") (pin "22") (pinfunction "22_22") (pintype "passive"))
      (node (ref "B2") (pin "N1") (pinfunction "P$2_N1") (pintype "bidirectional"))
    )
    (net (code "106") (name "Net-(B1X-P$2)") (class "Default")
      (node (ref "B1") (pin "N2") (pinfunction "P$2_N2") (pintype "bidirectional"))
      (node (ref "B1B2SIDE2") (pin "22") (pinfunction "22_22") (pintype "passive"))
      (node (ref "B2") (pin "N2") (pinfunction "P$2_N2") (pintype "bidirectional"))
    )
    (net (code "107") (name "Net-(B1Y-P$2)") (class "Default")
      (node (ref "B1") (pin "P1") (pinfunction "P$2_P1") (pintype "bidirectional"))
      (node (ref "B1B2SIDE1") (pin "30") (pinfunction "30_30") (pintype "passive"))
      (node (ref "B2") (pin "P1") (pinfunction "P$2_P1") (pintype "bidirectional"))
    )
    (net (code "108") (name "Net-(B1Z-P$2)") (class "Default")
      (node (ref "B1") (pin "P2") (pinfunction "P$2_P2") (pintype "bidirectional"))
      (node (ref "B1B2SIDE2") (pin "24") (pinfunction "24_24") (pintype "passive"))
      (node (ref "B2") (pin "P2") (pinfunction "P$2_P2") (pintype "bidirectional"))
    )
    (net (code "109") (name "Net-(B3A-P$2)") (class "Default")
      (node (ref "B3") (pin "A1") (pinfunction "P$2_A1") (pintype "bidirectional"))
      (node (ref "B3B4SIDE1") (pin "10") (pinfunction "10_10") (pintype "passive"))
      (node (ref "B4") (pin "A1") (pinfunction "P$2_A1") (pintype "bidirectional"))
    )
    (net (code "110") (name "Net-(B3AA-P$2)") (class "Default")
      (node (ref "B3") (pin "R1") (pinfunction "P$2_R1") (pintype "bidirectional"))
      (node (ref "B3B4SIDE1") (pin "26") (pinfunction "26_26") (pintype "passive"))
      (node (ref "B4") (pin "R1") (pinfunction "P$2_R1") (pintype "bidirectional"))
    )
    (net (code "111") (name "Net-(B3AB-P$2)") (class "Default")
      (node (ref "B3") (pin "R2") (pinfunction "P$2_R2") (pintype "bidirectional"))
      (node (ref "B3B4SIDE2") (pin "26") (pinfunction "26_26") (pintype "passive"))
      (node (ref "B4") (pin "R2") (pinfunction "P$2_R2") (pintype "bidirectional"))
    )
    (net (code "112") (name "Net-(B3AC-P$2)") (class "Default")
      (node (ref "B3") (pin "S1") (pinfunction "P$2_S1") (pintype "bidirectional"))
      (node (ref "B3B4SIDE1") (pin "32") (pinfunction "32_32") (pintype "passive"))
      (node (ref "B4") (pin "S1") (pinfunction "P$2_S1") (pintype "bidirectional"))
    )
    (net (code "113") (name "Net-(B3AD-P$2)") (class "Default")
      (node (ref "B3") (pin "S2") (pinfunction "P$2_S2") (pintype "bidirectional"))
      (node (ref "B3B4SIDE2") (pin "28") (pinfunction "28_28") (pintype "passive"))
      (node (ref "B4") (pin "S2") (pinfunction "P$2_S2") (pintype "bidirectional"))
    )
    (net (code "114") (name "Net-(B3AE-P$2)") (class "Default")
      (node (ref "B3") (pin "T1") (pinfunction "P$2_T1") (pintype "bidirectional"))
      (node (ref "B3B4SIDE1") (pin "34") (pinfunction "34_34") (pintype "passive"))
      (node (ref "B4") (pin "T1") (pinfunction "P$2_T1") (pintype "bidirectional"))
    )
    (net (code "115") (name "Net-(B3AF-P$2)") (class "Default")
      (node (ref "B3") (pin "T2") (pinfunction "P$2_T2") (pintype "bidirectional"))
      (node (ref "B3B4SIDE2") (pin "30") (pinfunction "30_30") (pintype "passive"))
      (node (ref "B4") (pin "T2") (pinfunction "P$2_T2") (pintype "bidirectional"))
    )
    (net (code "116") (name "Net-(B3AG-P$2)") (class "Default")
      (node (ref "B3") (pin "U1") (pinfunction "P$2_U1") (pintype "bidirectional"))
      (node (ref "B3B4SIDE1") (pin "4") (pinfunction "4_4") (pintype "passive"))
      (node (ref "B4") (pin "U1") (pinfunction "P$2_U1") (pintype "bidirectional"))
    )
    (net (code "117") (name "Net-(B3AH-P$2)") (class "Default")
      (node (ref "B3") (pin "U2") (pinfunction "P$2_U2") (pintype "bidirectional"))
      (node (ref "B3B4SIDE2") (pin "34") (pinfunction "34_34") (pintype "passive"))
      (node (ref "B4") (pin "U2") (pinfunction "P$2_U2") (pintype "bidirectional"))
    )
    (net (code "118") (name "Net-(B3AI-P$2)") (class "Default")
      (node (ref "B3") (pin "V1") (pinfunction "P$2_V1") (pintype "bidirectional"))
      (node (ref "B3B4SIDE1") (pin "2") (pinfunction "2_2") (pintype "passive"))
      (node (ref "B4") (pin "V1") (pinfunction "P$2_V1") (pintype "bidirectional"))
    )
    (net (code "119") (name "Net-(B3AJ-P$2)") (class "Default")
      (node (ref "B3") (pin "V2") (pinfunction "P$2_V2") (pintype "bidirectional"))
      (node (ref "B3B4SIDE2") (pin "32") (pinfunction "32_32") (pintype "passive"))
      (node (ref "B4") (pin "V2") (pinfunction "P$2_V2") (pintype "bidirectional"))
    )
    (net (code "120") (name "Net-(B3B-P$2)") (class "Default")
      (node (ref "B3") (pin "A2") (pinfunction "P$2_A2") (pintype "bidirectional"))
      (node (ref "B3B4SIDE2") (pin "2") (pinfunction "2_2") (pintype "passive"))
      (node (ref "B4") (pin "A2") (pinfunction "P$2_A2") (pintype "bidirectional"))
    )
    (net (code "121") (name "Net-(B3C-P$2)") (class "Default")
      (node (ref "B3") (pin "B1") (pinfunction "P$2_B1") (pintype "bidirectional"))
      (node (ref "B3B4SIDE1") (pin "6") (pinfunction "6_6") (pintype "passive"))
      (node (ref "B4") (pin "B1") (pinfunction "P$2_B1") (pintype "bidirectional"))
    )
    (net (code "122") (name "Net-(B3D-P$2)") (class "Default")
      (node (ref "B3") (pin "B2") (pinfunction "P$2_B2") (pintype "bidirectional"))
      (node (ref "B3B4SIDE2") (pin "4") (pinfunction "4_4") (pintype "passive"))
      (node (ref "B4") (pin "B2") (pinfunction "P$2_B2") (pintype "bidirectional"))
    )
    (net (code "123") (name "Net-(B3E-P$2)") (class "Default")
      (node (ref "B3") (pin "C1") (pinfunction "P$2_C1") (pintype "bidirectional"))
      (node (ref "B3B4SIDE1") (pin "1") (pinfunction "1_1") (pintype "passive"))
      (node (ref "B3B4SIDE1") (pin "11") (pinfunction "11_11") (pintype "passive"))
      (node (ref "B3B4SIDE1") (pin "13") (pinfunction "13_13") (pintype "passive"))
      (node (ref "B3B4SIDE1") (pin "15") (pinfunction "15_15") (pintype "passive"))
      (node (ref "B3B4SIDE1") (pin "17") (pinfunction "17_17") (pintype "passive"))
      (node (ref "B3B4SIDE1") (pin "19") (pinfunction "19_19") (pintype "passive"))
      (node (ref "B3B4SIDE1") (pin "21") (pinfunction "21_21") (pintype "passive"))
      (node (ref "B3B4SIDE1") (pin "23") (pinfunction "23_23") (pintype "passive"))
      (node (ref "B3B4SIDE1") (pin "25") (pinfunction "25_25") (pintype "passive"))
      (node (ref "B3B4SIDE1") (pin "27") (pinfunction "27_27") (pintype "passive"))
      (node (ref "B3B4SIDE1") (pin "29") (pinfunction "29_29") (pintype "passive"))
      (node (ref "B3B4SIDE1") (pin "3") (pinfunction "3_3") (pintype "passive"))
      (node (ref "B3B4SIDE1") (pin "31") (pinfunction "31_31") (pintype "passive"))
      (node (ref "B3B4SIDE1") (pin "33") (pinfunction "33_33") (pintype "passive"))
      (node (ref "B3B4SIDE1") (pin "5") (pinfunction "5_5") (pintype "passive"))
      (node (ref "B3B4SIDE1") (pin "7") (pinfunction "7_7") (pintype "passive"))
      (node (ref "B3B4SIDE1") (pin "9") (pinfunction "9_9") (pintype "passive"))
      (node (ref "B4") (pin "C1") (pinfunction "P$2_C1") (pintype "bidirectional"))
    )
    (net (code "124") (name "Net-(B3F-P$2)") (class "Default")
      (node (ref "B3") (pin "C2") (pinfunction "P$2_C2") (pintype "bidirectional"))
      (node (ref "B3B4SIDE2") (pin "1") (pinfunction "1_1") (pintype "passive"))
      (node (ref "B3B4SIDE2") (pin "11") (pinfunction "11_11") (pintype "passive"))
      (node (ref "B3B4SIDE2") (pin "13") (pinfunction "13_13") (pintype "passive"))
      (node (ref "B3B4SIDE2") (pin "15") (pinfunction "15_15") (pintype "passive"))
      (node (ref "B3B4SIDE2") (pin "17") (pinfunction "17_17") (pintype "passive"))
      (node (ref "B3B4SIDE2") (pin "19") (pinfunction "19_19") (pintype "passive"))
      (node (ref "B3B4SIDE2") (pin "21") (pinfunction "21_21") (pintype "passive"))
      (node (ref "B3B4SIDE2") (pin "23") (pinfunction "23_23") (pintype "passive"))
      (node (ref "B3B4SIDE2") (pin "25") (pinfunction "25_25") (pintype "passive"))
      (node (ref "B3B4SIDE2") (pin "27") (pinfunction "27_27") (pintype "passive"))
      (node (ref "B3B4SIDE2") (pin "29") (pinfunction "29_29") (pintype "passive"))
      (node (ref "B3B4SIDE2") (pin "3") (pinfunction "3_3") (pintype "passive"))
      (node (ref "B3B4SIDE2") (pin "31") (pinfunction "31_31") (pintype "passive"))
      (node (ref "B3B4SIDE2") (pin "33") (pinfunction "33_33") (pintype "passive"))
      (node (ref "B3B4SIDE2") (pin "5") (pinfunction "5_5") (pintype "passive"))
      (node (ref "B3B4SIDE2") (pin "7") (pinfunction "7_7") (pintype "passive"))
      (node (ref "B3B4SIDE2") (pin "9") (pinfunction "9_9") (pintype "passive"))
      (node (ref "B4") (pin "C2") (pinfunction "P$2_C2") (pintype "bidirectional"))
    )
    (net (code "125") (name "Net-(B3G-P$2)") (class "Default")
      (node (ref "B3") (pin "D1") (pinfunction "P$2_D1") (pintype "bidirectional"))
      (node (ref "B3B4SIDE1") (pin "8") (pinfunction "8_8") (pintype "passive"))
      (node (ref "B4") (pin "D1") (pinfunction "P$2_D1") (pintype "bidirectional"))
    )
    (net (code "126") (name "Net-(B3H-P$2)") (class "Default")
      (node (ref "B3") (pin "D2") (pinfunction "P$2_D2") (pintype "bidirectional"))
      (node (ref "B3B4SIDE2") (pin "6") (pinfunction "6_6") (pintype "passive"))
      (node (ref "B4") (pin "D2") (pinfunction "P$2_D2") (pintype "bidirectional"))
    )
    (net (code "127") (name "Net-(B3I-P$2)") (class "Default")
      (node (ref "B3") (pin "E1") (pinfunction "P$2_E1") (pintype "bidirectional"))
      (node (ref "B3B4SIDE1") (pin "12") (pinfunction "12_12") (pintype "passive"))
      (node (ref "B4") (pin "E1") (pinfunction "P$2_E1") (pintype "bidirectional"))
    )
    (net (code "128") (name "Net-(B3J-P$2)") (class "Default")
      (node (ref "B3") (pin "E2") (pinfunction "P$2_E2") (pintype "bidirectional"))
      (node (ref "B3B4SIDE2") (pin "8") (pinfunction "8_8") (pintype "passive"))
      (node (ref "B4") (pin "E2") (pinfunction "P$2_E2") (pintype "bidirectional"))
    )
    (net (code "129") (name "Net-(B3K-P$2)") (class "Default")
      (node (ref "B3") (pin "F1") (pinfunction "P$2_F1") (pintype "bidirectional"))
      (node (ref "B3B4SIDE1") (pin "14") (pinfunction "14_14") (pintype "passive"))
      (node (ref "B4") (pin "F1") (pinfunction "P$2_F1") (pintype "bidirectional"))
    )
    (net (code "130") (name "Net-(B3L-P$2)") (class "Default")
      (node (ref "B3") (pin "F2") (pinfunction "P$2_F2") (pintype "bidirectional"))
      (node (ref "B3B4SIDE2") (pin "10") (pinfunction "10_10") (pintype "passive"))
      (node (ref "B4") (pin "F2") (pinfunction "P$2_F2") (pintype "bidirectional"))
    )
    (net (code "131") (name "Net-(B3M-P$2)") (class "Default")
      (node (ref "B3") (pin "H1") (pinfunction "P$2_H1") (pintype "bidirectional"))
      (node (ref "B3B4SIDE1") (pin "16") (pinfunction "16_16") (pintype "passive"))
      (node (ref "B4") (pin "H1") (pinfunction "P$2_H1") (pintype "bidirectional"))
    )
    (net (code "132") (name "Net-(B3N-P$2)") (class "Default")
      (node (ref "B3") (pin "H2") (pinfunction "P$2_H2") (pintype "bidirectional"))
      (node (ref "B3B4SIDE2") (pin "12") (pinfunction "12_12") (pintype "passive"))
      (node (ref "B4") (pin "H2") (pinfunction "P$2_H2") (pintype "bidirectional"))
    )
    (net (code "133") (name "Net-(B3O-P$2)") (class "Default")
      (node (ref "B3") (pin "J1") (pinfunction "P$2_J1") (pintype "bidirectional"))
      (node (ref "B3B4SIDE1") (pin "20") (pinfunction "20_20") (pintype "passive"))
      (node (ref "B4") (pin "J1") (pinfunction "P$2_J1") (pintype "bidirectional"))
    )
    (net (code "134") (name "Net-(B3P-P$2)") (class "Default")
      (node (ref "B3") (pin "J2") (pinfunction "P$2_J2") (pintype "bidirectional"))
      (node (ref "B3B4SIDE2") (pin "14") (pinfunction "14_14") (pintype "passive"))
      (node (ref "B4") (pin "J2") (pinfunction "P$2_J2") (pintype "bidirectional"))
    )
    (net (code "135") (name "Net-(B3Q-P$2)") (class "Default")
      (node (ref "B3") (pin "K1") (pinfunction "P$2_K1") (pintype "bidirectional"))
      (node (ref "B3B4SIDE1") (pin "18") (pinfunction "18_18") (pintype "passive"))
      (node (ref "B4") (pin "K1") (pinfunction "P$2_K1") (pintype "bidirectional"))
    )
    (net (code "136") (name "Net-(B3R-P$2)") (class "Default")
      (node (ref "B3") (pin "K2") (pinfunction "P$2_K2") (pintype "bidirectional"))
      (node (ref "B3B4SIDE2") (pin "16") (pinfunction "16_16") (pintype "passive"))
      (node (ref "B4") (pin "K2") (pinfunction "P$2_K2") (pintype "bidirectional"))
    )
    (net (code "137") (name "Net-(B3S-P$2)") (class "Default")
      (node (ref "B3") (pin "L1") (pinfunction "P$2_L1") (pintype "bidirectional"))
      (node (ref "B3B4SIDE1") (pin "24") (pinfunction "24_24") (pintype "passive"))
      (node (ref "B4") (pin "L1") (pinfunction "P$2_L1") (pintype "bidirectional"))
    )
    (net (code "138") (name "Net-(B3T-P$2)") (class "Default")
      (node (ref "B3") (pin "L2") (pinfunction "P$2_L2") (pintype "bidirectional"))
      (node (ref "B3B4SIDE2") (pin "18") (pinfunction "18_18") (pintype "passive"))
      (node (ref "B4") (pin "L2") (pinfunction "P$2_L2") (pintype "bidirectional"))
    )
    (net (code "139") (name "Net-(B3U-P$2)") (class "Default")
      (node (ref "B3") (pin "M1") (pinfunction "P$2_M1") (pintype "bidirectional"))
      (node (ref "B3B4SIDE1") (pin "28") (pinfunction "28_28") (pintype "passive"))
      (node (ref "B4") (pin "M1") (pinfunction "P$2_M1") (pintype "bidirectional"))
    )
    (net (code "140") (name "Net-(B3V-P$2)") (class "Default")
      (node (ref "B3") (pin "M2") (pinfunction "P$2_M2") (pintype "bidirectional"))
      (node (ref "B3B4SIDE2") (pin "20") (pinfunction "20_20") (pintype "passive"))
      (node (ref "B4") (pin "M2") (pinfunction "P$2_M2") (pintype "bidirectional"))
    )
    (net (code "141") (name "Net-(B3W-P$2)") (class "Default")
      (node (ref "B3") (pin "N1") (pinfunction "P$2_N1") (pintype "bidirectional"))
      (node (ref "B3B4SIDE1") (pin "22") (pinfunction "22_22") (pintype "passive"))
      (node (ref "B4") (pin "N1") (pinfunction "P$2_N1") (pintype "bidirectional"))
    )
    (net (code "142") (name "Net-(B3X-P$2)") (class "Default")
      (node (ref "B3") (pin "N2") (pinfunction "P$2_N2") (pintype "bidirectional"))
      (node (ref "B3B4SIDE2") (pin "22") (pinfunction "22_22") (pintype "passive"))
      (node (ref "B4") (pin "N2") (pinfunction "P$2_N2") (pintype "bidirectional"))
    )
    (net (code "143") (name "Net-(B3Y-P$2)") (class "Default")
      (node (ref "B3") (pin "P1") (pinfunction "P$2_P1") (pintype "bidirectional"))
      (node (ref "B3B4SIDE1") (pin "30") (pinfunction "30_30") (pintype "passive"))
      (node (ref "B4") (pin "P1") (pinfunction "P$2_P1") (pintype "bidirectional"))
    )
    (net (code "144") (name "Net-(B3Z-P$2)") (class "Default")
      (node (ref "B3") (pin "P2") (pinfunction "P$2_P2") (pintype "bidirectional"))
      (node (ref "B3B4SIDE2") (pin "24") (pinfunction "24_24") (pintype "passive"))
      (node (ref "B4") (pin "P2") (pinfunction "P$2_P2") (pintype "bidirectional"))
    )
  )
)
